# button.net
KiCad netlist of a schematic drawn in EAGLE
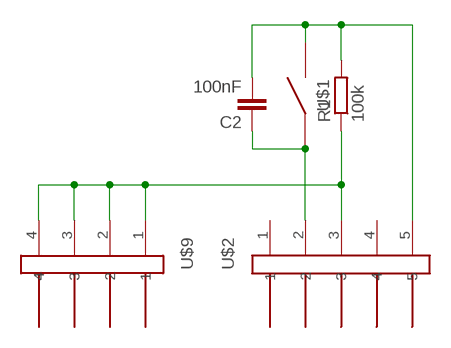
[diagram p0: schematic, sheet 1]

(export (version "E")
  (design (tool "Eeschema 10.0.6"))
  (components
    (comp (ref "C2")
      (value "100nF")
      (footprint "eagle-import:C0603K")
      (libsource (lib "eagle-import") (part "C-EUC0603K"))
    )
    (comp (ref "R1")
      (value "100k")
      (footprint "eagle-import:R0603")
      (libsource (lib "eagle-import") (part "R-EU_R0603"))
    )
    (comp (ref "U$1")
      (value "BUTTON_7X7")
      (footprint "eagle-import:BUTTON_7X7")
      (libsource (lib "eagle-import") (part "BUTTON_7X7"))
    )
    (comp (ref "U$2")
      (value "JUMPER5M")
      (footprint "eagle-import:JUMPER5M")
      (libsource (lib "eagle-import") (part "JUMPER5M"))
    )
    (comp (ref "U$9")
      (value "JUMPER4M")
      (footprint "eagle-import:JUMPER4M")
      (libsource (lib "eagle-import") (part "JUMPER4M"))
    )
  )
  (nets
    (net (code "1") (name "Net-(C2-Pad1)") (class "Default")
      (node (ref "C2") (pin "1") (pinfunction "1_1") (pintype "passive"))
      (node (ref "U$1") (pin "A1") (pinfunction "P$1_A1") (pintype "bidirectional"))
      (node (ref "U$1") (pin "A2") (pinfunction "P$1_A2") (pintype "bidirectional"))
      (node (ref "U$2") (pin "2") (pinfunction "2_2") (pintype "bidirectional"))
    )
    (net (code "2") (name "Net-(C2-Pad2)") (class "Default")
      (node (ref "C2") (pin "2") (pinfunction "2_2") (pintype "passive"))
      (node (ref "R1") (pin "2") (pinfunction "2_2") (pintype "passive"))
      (node (ref "U$1") (pin "B1") (pinfunction "P$2_B1") (pintype "bidirectional"))
      (node (ref "U$1") (pin "B2") (pinfunction "P$2_B2") (pintype "bidirectional"))
      (node (ref "U$2") (pin "5") (pinfunction "5_5") (pintype "bidirectional"))
    )
    (net (code "3") (name "Net-(R1-Pad1)") (class "Default")
      (node (ref "R1") (pin "1") (pinfunction "1_1") (pintype "passive"))
      (node (ref "U$2") (pin "3") (pinfunction "3_3") (pintype "bidirectional"))
      (node (ref "U$9") (pin "1") (pinfunction "1_1") (pintype "bidirectional"))
      (node (ref "U$9") (pin "2") (pinfunction "2_2") (pintype "bidirectional"))
      (node (ref "U$9") (pin "3") (pinfunction "3_3") (pintype "bidirectional"))
      (node (ref "U$9") (pin "4") (pinfunction "4_4") (pintype "bidirectional"))
    )
    (net (code "4") (name "unconnected-(U$2-Pad1)") (class "Default")
      (node (ref "U$2") (pin "1") (pinfunction "1_1") (pintype "bidirectional"))
    )
    (net (code "5") (name "unconnected-(U$2-Pad4)") (class "Default")
      (node (ref "U$2") (pin "4") (pinfunction "4_4") (pintype "bidirectional"))
    )
  )
)
